# SCH_regulador_carga_2025-11-12.net
KiCad netlist of a schematic drawn in EasyEDA
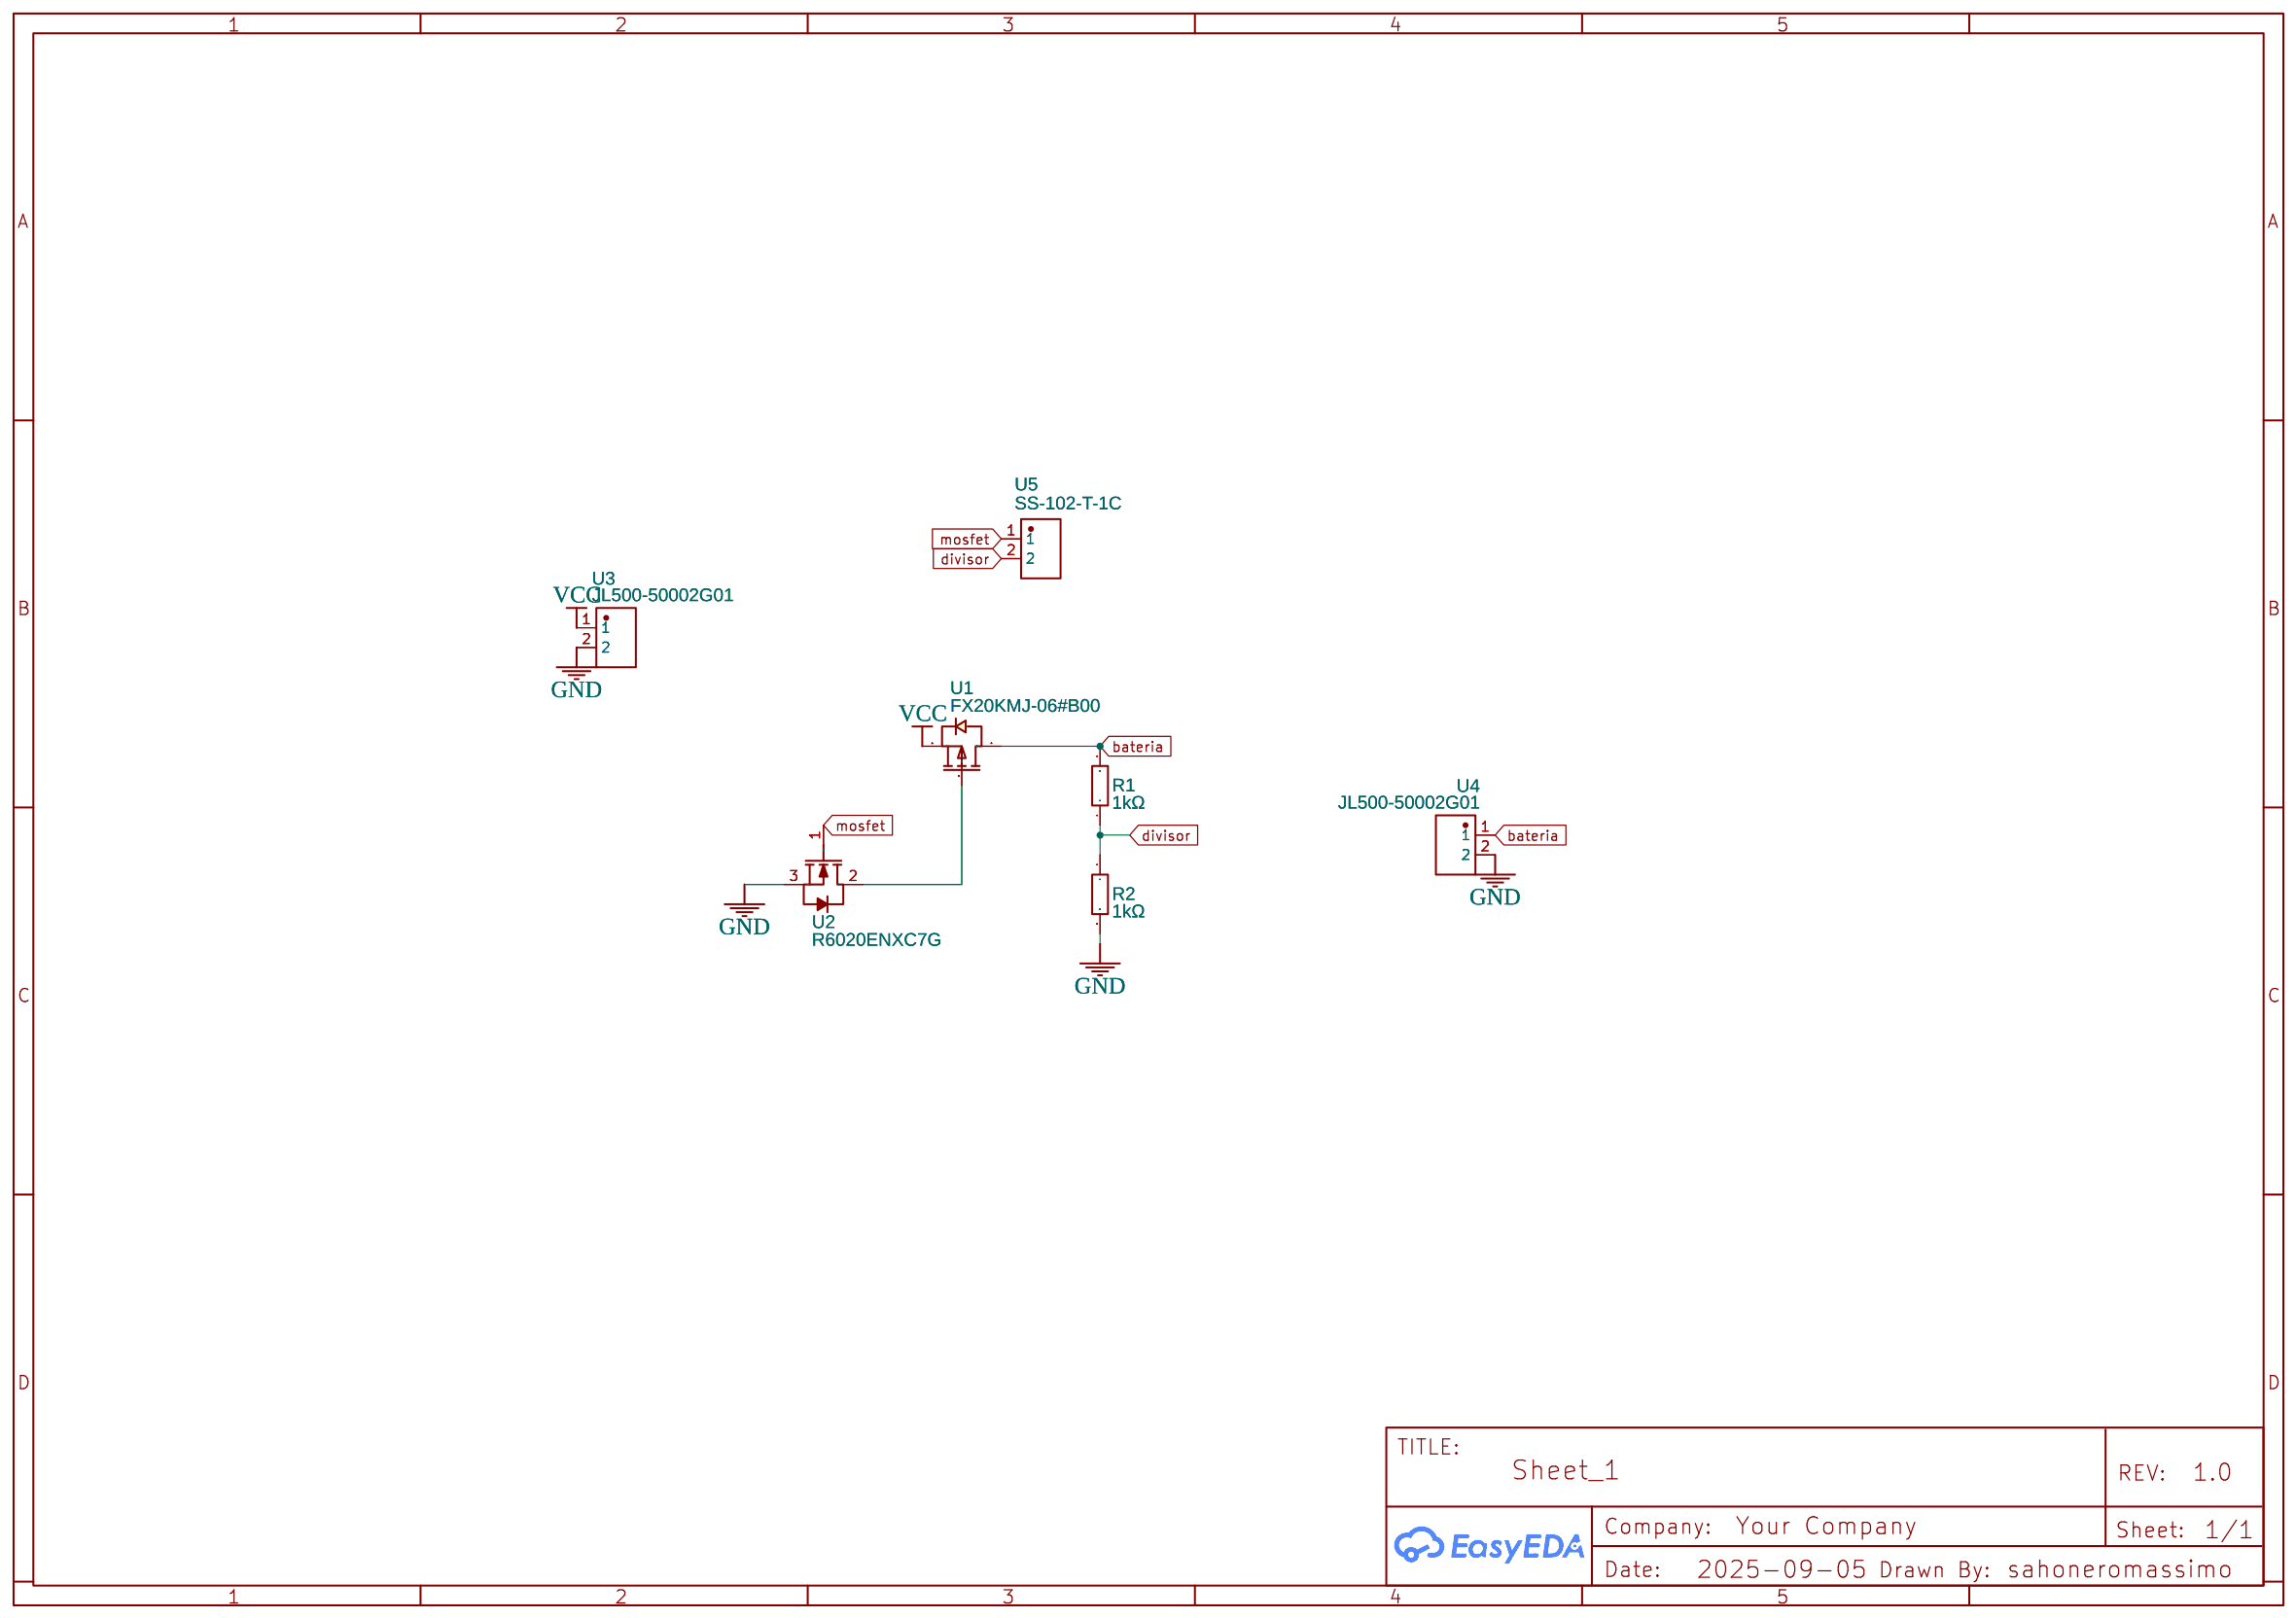
[diagram p0: schematic sheet]

(export (version "E")
  (design (tool "Eeschema 10.0.6"))
  (components
    (comp (ref "R1")
      (value "1kΩ")
      (fields
        (field (name "Manufacturer Part") "CFR0W4J0242A50")
        (field (name "Manufacturer") "UNI-ROYAL(厚声)")
      )
      (libsource (lib "") (part "CFR0W4J0242A50_1"))
    )
    (comp (ref "R2")
      (value "1kΩ")
      (fields
        (field (name "Manufacturer Part") "CFR0W4J0242A50")
        (field (name "Manufacturer") "UNI-ROYAL(厚声)")
      )
      (libsource (lib "") (part "CFR0W4J0242A50"))
    )
    (comp (ref "U1")
      (value "FX20KMJ-06#B00")
      (fields (field (name "Manufacturer") "RENESAS(瑞萨)/IDT"))
      (libsource (lib "") (part "FX20KMJ-06#B00"))
    )
    (comp (ref "U2")
      (value "R6020ENXC7G")
      (fields (field (name "Manufacturer") "ROHM(罗姆)"))
      (libsource (lib "") (part "R6020ENXC7G"))
    )
    (comp (ref "U3")
      (value "JL500-50002G01")
      (fields (field (name "Manufacturer") "JILN(锦凌)"))
      (libsource (lib "") (part "JL500-50002G01"))
    )
    (comp (ref "U4")
      (value "JL500-50002G01")
      (fields (field (name "Manufacturer") "JILN(锦凌)"))
      (libsource (lib "") (part "JL500-50002G01_1"))
    )
    (comp (ref "U5")
      (value "SS-102-T-1C")
      (fields (field (name "Manufacturer") "SAMTEC"))
      (libsource (lib "") (part "SS-102-T-1C"))
    )
  )
  (nets
    (net (code "1") (name "GND") (class "Default")
      (node (ref "R2") (pin "2") (pinfunction "2_2") (pintype "unspecified"))
      (node (ref "U2") (pin "3") (pinfunction "S_3") (pintype "unspecified"))
      (node (ref "U3") (pin "2") (pinfunction "2_2") (pintype "unspecified"))
      (node (ref "U4") (pin "2") (pinfunction "2_2") (pintype "unspecified"))
    )
    (net (code "2") (name "Net-(U1-G)") (class "Default")
      (node (ref "U1") (pin "1") (pinfunction "G_1") (pintype "unspecified"))
      (node (ref "U2") (pin "2") (pinfunction "D_2") (pintype "unspecified"))
    )
    (net (code "3") (name "VCC") (class "Default")
      (node (ref "U1") (pin "3") (pinfunction "S_3") (pintype "unspecified"))
      (node (ref "U3") (pin "1") (pinfunction "1_1") (pintype "unspecified"))
    )
    (net (code "4") (name "bateria") (class "Default")
      (node (ref "R1") (pin "2") (pinfunction "2_2") (pintype "unspecified"))
      (node (ref "U1") (pin "2") (pinfunction "D_2") (pintype "unspecified"))
      (node (ref "U4") (pin "1") (pinfunction "1_1") (pintype "unspecified"))
    )
    (net (code "5") (name "divisor") (class "Default")
      (node (ref "R1") (pin "1") (pinfunction "1_1") (pintype "unspecified"))
      (node (ref "R2") (pin "1") (pinfunction "1_1") (pintype "unspecified"))
      (node (ref "U5") (pin "2") (pinfunction "2_2") (pintype "unspecified"))
    )
    (net (code "6") (name "mosfet") (class "Default")
      (node (ref "U2") (pin "1") (pinfunction "G_1") (pintype "unspecified"))
      (node (ref "U5") (pin "1") (pinfunction "1_1") (pintype "unspecified"))
    )
  )
)
